# STM32.net
KiCad netlist of a schematic drawn in Altium Designer
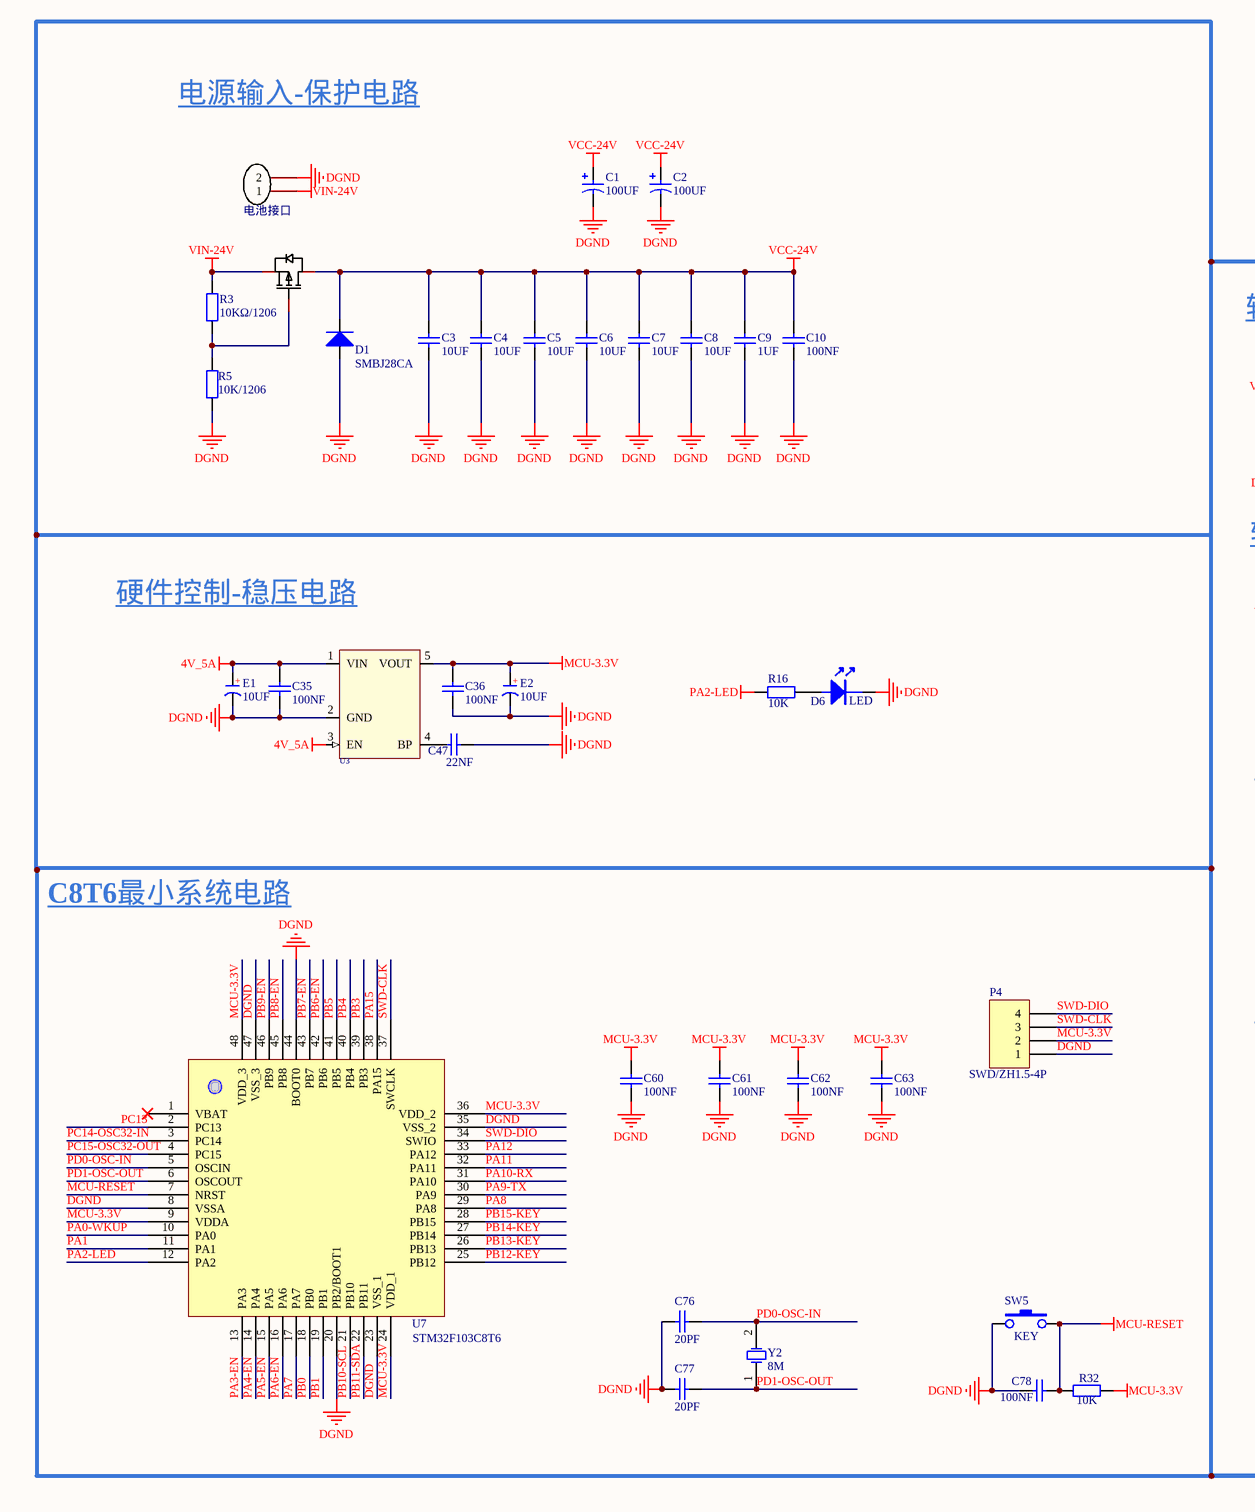
[diagram p0: 稳压板STM32.SchDoc, left]
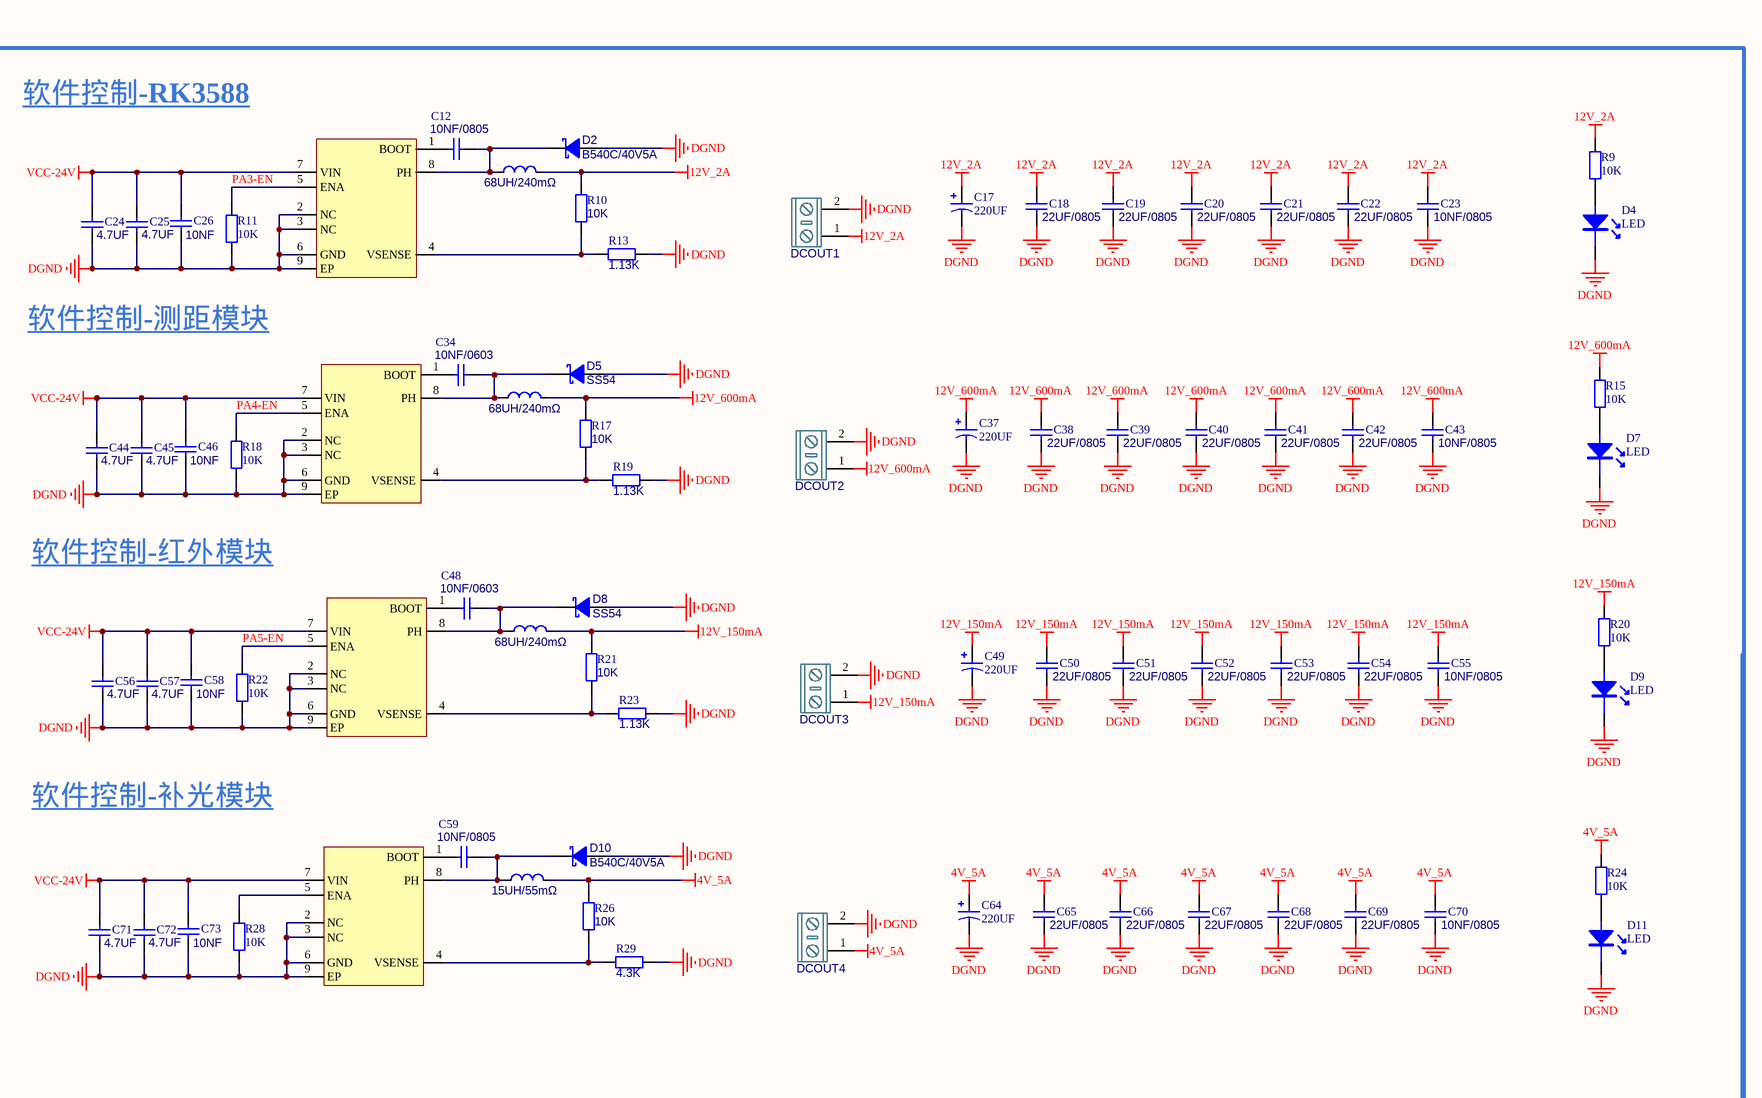
[diagram p1: 稳压板STM32.SchDoc, right]

(export (version "E")
  (design (tool "Eeschema 10.0.6"))
  (components
    (comp (ref "1")
      (value "68UH/240mΩ")
      (footprint "IND-SMD_L11.5-W10.0_SMMS1040")
      (fields
        (field (name "MANUFACTURER") "PANASONIC(松下)")
        (field (name "MANUFACTURER PART") "ETQP5M220YFM")
        (field (name "TOLERANCE") "±20%")
      )
      (libsource (lib "C8T6主控") (part "L?"))
    )
    (comp (ref "3")
      (value "68UH/240mΩ")
      (footprint "IND-SMD_L11.5-W10.0_SMMS1040")
      (fields
        (field (name "MANUFACTURER") "PANASONIC(松下)")
        (field (name "MANUFACTURER PART") "ETQP5M220YFM")
        (field (name "TOLERANCE") "±20%")
      )
      (libsource (lib "") (part "L?_1"))
    )
    (comp (ref "4")
      (value "68UH/240mΩ")
      (footprint "IND-SMD_L11.5-W10.0_SMMS1040")
      (fields
        (field (name "MANUFACTURER") "PANASONIC(松下)")
        (field (name "MANUFACTURER PART") "ETQP5M220YFM")
        (field (name "TOLERANCE") "±20%")
      )
      (libsource (lib "") (part "L?_3"))
    )
    (comp (ref "5")
      (value "15UH/55mΩ")
      (footprint "IND-SMD_L11.5-W10.0_SMMS1040")
      (fields
        (field (name "MANUFACTURER") "PANASONIC(松下)")
        (field (name "MANUFACTURER PART") "ETQP5M220YFM")
        (field (name "TOLERANCE") "±20%")
      )
      (libsource (lib "") (part "L?_2"))
    )
    (comp (ref "C1")
      (value "100UF")
      (footprint "CM D(6.3*7.7)")
      (description "有极性电容")
      (fields (field (name "PUBLISHER") "Altium Limited"))
      (libsource (lib "C8T6主控") (part "Cap Pol"))
    )
    (comp (ref "C2")
      (value "100UF")
      (footprint "CM D(6.3*7.7)")
      (description "有极性电容")
      (fields (field (name "PUBLISHER") "Altium Limited"))
      (libsource (lib "C8T6主控") (part "Cap Pol"))
    )
    (comp (ref "C3")
      (value "10UF")
      (footprint "C0603")
      (description "Capacitor")
      (fields (field (name "PUBLISHER") "Altium Limited"))
      (libsource (lib "STM32F103C8T6") (part "Cap"))
    )
    (comp (ref "C4")
      (value "10UF")
      (footprint "C0603")
      (description "Capacitor")
      (fields (field (name "PUBLISHER") "Altium Limited"))
      (libsource (lib "STM32F103C8T6") (part "Cap"))
    )
    (comp (ref "C5")
      (value "10UF")
      (footprint "C0603")
      (description "Capacitor")
      (fields (field (name "PUBLISHER") "Altium Limited"))
      (libsource (lib "STM32F103C8T6") (part "Cap"))
    )
    (comp (ref "C6")
      (value "10UF")
      (footprint "C0603")
      (description "Capacitor")
      (fields (field (name "PUBLISHER") "Altium Limited"))
      (libsource (lib "STM32F103C8T6") (part "Cap"))
    )
    (comp (ref "C7")
      (value "10UF")
      (footprint "C0603")
      (description "Capacitor")
      (fields (field (name "PUBLISHER") "Altium Limited"))
      (libsource (lib "STM32F103C8T6") (part "Cap"))
    )
    (comp (ref "C8")
      (value "10UF")
      (footprint "C0603")
      (description "Capacitor")
      (fields (field (name "PUBLISHER") "Altium Limited"))
      (libsource (lib "STM32F103C8T6") (part "Cap"))
    )
    (comp (ref "C9")
      (value "1UF")
      (footprint "C0603")
      (description "Capacitor")
      (fields (field (name "PUBLISHER") "Altium Limited"))
      (libsource (lib "STM32F103C8T6") (part "Cap"))
    )
    (comp (ref "C10")
      (value "100NF")
      (footprint "C0603")
      (description "Capacitor")
      (fields (field (name "PUBLISHER") "Altium Limited"))
      (libsource (lib "STM32F103C8T6") (part "Cap"))
    )
    (comp (ref "C12")
      (value "10NF/0805")
      (footprint "C0805")
      (description "Capacitor")
      (fields (field (name "PUBLISHER") "Altium Limited"))
      (libsource (lib "STM32F103C8T6") (part "Cap"))
    )
    (comp (ref "C17")
      (value "220UF")
      (footprint "CM F(10*10.2)")
      (description "有极性电容")
      (fields (field (name "PUBLISHER") "Altium Limited"))
      (libsource (lib "C8T6主控") (part "Cap Pol"))
    )
    (comp (ref "C18")
      (value "22UF/0805")
      (footprint "C0805")
      (description "Capacitor")
      (fields (field (name "PUBLISHER") "Altium Limited"))
      (libsource (lib "STM32F103C8T6") (part "Cap"))
    )
    (comp (ref "C19")
      (value "22UF/0805")
      (footprint "C0805")
      (description "Capacitor")
      (fields (field (name "PUBLISHER") "Altium Limited"))
      (libsource (lib "STM32F103C8T6") (part "Cap"))
    )
    (comp (ref "C20")
      (value "22UF/0805")
      (footprint "C0805")
      (description "Capacitor")
      (fields (field (name "PUBLISHER") "Altium Limited"))
      (libsource (lib "STM32F103C8T6") (part "Cap"))
    )
    (comp (ref "C21")
      (value "22UF/0805")
      (footprint "C0805")
      (description "Capacitor")
      (fields (field (name "PUBLISHER") "Altium Limited"))
      (libsource (lib "STM32F103C8T6") (part "Cap"))
    )
    (comp (ref "C22")
      (value "22UF/0805")
      (footprint "C0805")
      (description "Capacitor")
      (fields (field (name "PUBLISHER") "Altium Limited"))
      (libsource (lib "STM32F103C8T6") (part "Cap"))
    )
    (comp (ref "C23")
      (value "10NF/0805")
      (footprint "C0805")
      (description "Capacitor")
      (fields (field (name "PUBLISHER") "Altium Limited"))
      (libsource (lib "STM32F103C8T6") (part "Cap"))
    )
    (comp (ref "C24")
      (value "4.7UF")
      (footprint "C1812")
      (description "Capacitor")
      (fields (field (name "PUBLISHER") "Altium Limited"))
      (libsource (lib "STM32F103C8T6") (part "Cap"))
    )
    (comp (ref "C25")
      (value "4.7UF")
      (footprint "C1812")
      (description "Capacitor")
      (fields (field (name "PUBLISHER") "Altium Limited"))
      (libsource (lib "STM32F103C8T6") (part "Cap"))
    )
    (comp (ref "C26")
      (value "10NF")
      (footprint "C0805")
      (description "Capacitor")
      (fields (field (name "PUBLISHER") "Altium Limited"))
      (libsource (lib "STM32F103C8T6") (part "Cap"))
    )
    (comp (ref "C34")
      (value "10NF/0603")
      (footprint "C0603")
      (description "Capacitor")
      (fields (field (name "PUBLISHER") "Altium Limited"))
      (libsource (lib "STM32F103C8T6") (part "Cap"))
    )
    (comp (ref "C35")
      (value "100NF")
      (footprint "C0603")
      (description "Capacitor")
      (fields (field (name "PUBLISHER") "Altium Limited"))
      (libsource (lib "STM32F103C8T6") (part "Cap"))
    )
    (comp (ref "C36")
      (value "100NF")
      (footprint "C0603")
      (description "Capacitor")
      (fields (field (name "PUBLISHER") "Altium Limited"))
      (libsource (lib "STM32F103C8T6") (part "Cap"))
    )
    (comp (ref "C37")
      (value "220UF")
      (footprint "CM F(10*10.2)")
      (description "有极性电容")
      (fields (field (name "PUBLISHER") "Altium Limited"))
      (libsource (lib "C8T6主控") (part "Cap Pol"))
    )
    (comp (ref "C38")
      (value "22UF/0805")
      (footprint "C0805")
      (description "Capacitor")
      (fields (field (name "PUBLISHER") "Altium Limited"))
      (libsource (lib "STM32F103C8T6") (part "Cap"))
    )
    (comp (ref "C39")
      (value "22UF/0805")
      (footprint "C0805")
      (description "Capacitor")
      (fields (field (name "PUBLISHER") "Altium Limited"))
      (libsource (lib "STM32F103C8T6") (part "Cap"))
    )
    (comp (ref "C40")
      (value "22UF/0805")
      (footprint "C0805")
      (description "Capacitor")
      (fields (field (name "PUBLISHER") "Altium Limited"))
      (libsource (lib "STM32F103C8T6") (part "Cap"))
    )
    (comp (ref "C41")
      (value "22UF/0805")
      (footprint "C0805")
      (description "Capacitor")
      (fields (field (name "PUBLISHER") "Altium Limited"))
      (libsource (lib "STM32F103C8T6") (part "Cap"))
    )
    (comp (ref "C42")
      (value "22UF/0805")
      (footprint "C0805")
      (description "Capacitor")
      (fields (field (name "PUBLISHER") "Altium Limited"))
      (libsource (lib "STM32F103C8T6") (part "Cap"))
    )
    (comp (ref "C43")
      (value "10NF/0805")
      (footprint "C0805")
      (description "Capacitor")
      (fields (field (name "PUBLISHER") "Altium Limited"))
      (libsource (lib "STM32F103C8T6") (part "Cap"))
    )
    (comp (ref "C44")
      (value "4.7UF")
      (footprint "C0603")
      (description "Capacitor")
      (fields (field (name "PUBLISHER") "Altium Limited"))
      (libsource (lib "STM32F103C8T6") (part "Cap"))
    )
    (comp (ref "C45")
      (value "4.7UF")
      (footprint "C0603")
      (description "Capacitor")
      (fields (field (name "PUBLISHER") "Altium Limited"))
      (libsource (lib "STM32F103C8T6") (part "Cap"))
    )
    (comp (ref "C46")
      (value "10NF")
      (footprint "C0603")
      (description "Capacitor")
      (fields (field (name "PUBLISHER") "Altium Limited"))
      (libsource (lib "STM32F103C8T6") (part "Cap"))
    )
    (comp (ref "C47")
      (value "22NF")
      (footprint "C0603")
      (description "Capacitor")
      (fields (field (name "PUBLISHER") "Altium Limited"))
      (libsource (lib "STM32F103C8T6") (part "Cap"))
    )
    (comp (ref "C48")
      (value "10NF/0603")
      (footprint "C0603")
      (description "Capacitor")
      (fields (field (name "PUBLISHER") "Altium Limited"))
      (libsource (lib "STM32F103C8T6") (part "Cap"))
    )
    (comp (ref "C49")
      (value "220UF")
      (footprint "CM F(10*10.2)")
      (description "有极性电容")
      (fields (field (name "PUBLISHER") "Altium Limited"))
      (libsource (lib "C8T6主控") (part "Cap Pol"))
    )
    (comp (ref "C50")
      (value "22UF/0805")
      (footprint "C0805")
      (description "Capacitor")
      (fields (field (name "PUBLISHER") "Altium Limited"))
      (libsource (lib "STM32F103C8T6") (part "Cap"))
    )
    (comp (ref "C51")
      (value "22UF/0805")
      (footprint "C0805")
      (description "Capacitor")
      (fields (field (name "PUBLISHER") "Altium Limited"))
      (libsource (lib "STM32F103C8T6") (part "Cap"))
    )
    (comp (ref "C52")
      (value "22UF/0805")
      (footprint "C0805")
      (description "Capacitor")
      (fields (field (name "PUBLISHER") "Altium Limited"))
      (libsource (lib "STM32F103C8T6") (part "Cap"))
    )
    (comp (ref "C53")
      (value "22UF/0805")
      (footprint "C0805")
      (description "Capacitor")
      (fields (field (name "PUBLISHER") "Altium Limited"))
      (libsource (lib "STM32F103C8T6") (part "Cap"))
    )
    (comp (ref "C54")
      (value "22UF/0805")
      (footprint "C0805")
      (description "Capacitor")
      (fields (field (name "PUBLISHER") "Altium Limited"))
      (libsource (lib "STM32F103C8T6") (part "Cap"))
    )
    (comp (ref "C55")
      (value "10NF/0805")
      (footprint "C0805")
      (description "Capacitor")
      (fields (field (name "PUBLISHER") "Altium Limited"))
      (libsource (lib "STM32F103C8T6") (part "Cap"))
    )
    (comp (ref "C56")
      (value "4.7UF")
      (footprint "C0603")
      (description "Capacitor")
      (fields (field (name "PUBLISHER") "Altium Limited"))
      (libsource (lib "STM32F103C8T6") (part "Cap"))
    )
    (comp (ref "C57")
      (value "4.7UF")
      (footprint "C0603")
      (description "Capacitor")
      (fields (field (name "PUBLISHER") "Altium Limited"))
      (libsource (lib "STM32F103C8T6") (part "Cap"))
    )
    (comp (ref "C58")
      (value "10NF")
      (footprint "C0603")
      (description "Capacitor")
      (fields (field (name "PUBLISHER") "Altium Limited"))
      (libsource (lib "STM32F103C8T6") (part "Cap"))
    )
    (comp (ref "C59")
      (value "10NF/0805")
      (footprint "C0805")
      (description "Capacitor")
      (fields (field (name "PUBLISHER") "Altium Limited"))
      (libsource (lib "STM32F103C8T6") (part "Cap"))
    )
    (comp (ref "C60")
      (value "100NF")
      (footprint "C0603")
      (description "Capacitor")
      (fields (field (name "PUBLISHER") "Altium Limited"))
      (libsource (lib "STM32F103C8T6") (part "Cap"))
    )
    (comp (ref "C61")
      (value "100NF")
      (footprint "C0603")
      (description "Capacitor")
      (fields (field (name "PUBLISHER") "Altium Limited"))
      (libsource (lib "STM32F103C8T6") (part "Cap"))
    )
    (comp (ref "C62")
      (value "100NF")
      (footprint "C0603")
      (description "Capacitor")
      (fields (field (name "PUBLISHER") "Altium Limited"))
      (libsource (lib "STM32F103C8T6") (part "Cap"))
    )
    (comp (ref "C63")
      (value "100NF")
      (footprint "C0603")
      (description "Capacitor")
      (fields (field (name "PUBLISHER") "Altium Limited"))
      (libsource (lib "STM32F103C8T6") (part "Cap"))
    )
    (comp (ref "C64")
      (value "220UF")
      (footprint "CM F(10*10.2)")
      (description "有极性电容")
      (fields (field (name "PUBLISHER") "Altium Limited"))
      (libsource (lib "C8T6主控") (part "Cap Pol"))
    )
    (comp (ref "C65")
      (value "22UF/0805")
      (footprint "C0805")
      (description "Capacitor")
      (fields (field (name "PUBLISHER") "Altium Limited"))
      (libsource (lib "STM32F103C8T6") (part "Cap"))
    )
    (comp (ref "C66")
      (value "22UF/0805")
      (footprint "C0805")
      (description "Capacitor")
      (fields (field (name "PUBLISHER") "Altium Limited"))
      (libsource (lib "STM32F103C8T6") (part "Cap"))
    )
    (comp (ref "C67")
      (value "22UF/0805")
      (footprint "C0805")
      (description "Capacitor")
      (fields (field (name "PUBLISHER") "Altium Limited"))
      (libsource (lib "STM32F103C8T6") (part "Cap"))
    )
    (comp (ref "C68")
      (value "22UF/0805")
      (footprint "C0805")
      (description "Capacitor")
      (fields (field (name "PUBLISHER") "Altium Limited"))
      (libsource (lib "STM32F103C8T6") (part "Cap"))
    )
    (comp (ref "C69")
      (value "22UF/0805")
      (footprint "C0805")
      (description "Capacitor")
      (fields (field (name "PUBLISHER") "Altium Limited"))
      (libsource (lib "STM32F103C8T6") (part "Cap"))
    )
    (comp (ref "C70")
      (value "10NF/0805")
      (footprint "C0805")
      (description "Capacitor")
      (fields (field (name "PUBLISHER") "Altium Limited"))
      (libsource (lib "STM32F103C8T6") (part "Cap"))
    )
    (comp (ref "C71")
      (value "4.7UF")
      (footprint "C1812")
      (description "Capacitor")
      (fields (field (name "PUBLISHER") "Altium Limited"))
      (libsource (lib "STM32F103C8T6") (part "Cap"))
    )
    (comp (ref "C72")
      (value "4.7UF")
      (footprint "C1812")
      (description "Capacitor")
      (fields (field (name "PUBLISHER") "Altium Limited"))
      (libsource (lib "STM32F103C8T6") (part "Cap"))
    )
    (comp (ref "C73")
      (value "10NF")
      (footprint "C0805")
      (description "Capacitor")
      (fields (field (name "PUBLISHER") "Altium Limited"))
      (libsource (lib "STM32F103C8T6") (part "Cap"))
    )
    (comp (ref "C76")
      (value "20PF")
      (footprint "C0603")
      (description "Capacitor")
      (fields (field (name "PUBLISHER") "Altium Limited"))
      (libsource (lib "STM32F103C8T6") (part "Cap"))
    )
    (comp (ref "C77")
      (value "20PF")
      (footprint "C0603")
      (description "Capacitor")
      (fields (field (name "PUBLISHER") "Altium Limited"))
      (libsource (lib "STM32F103C8T6") (part "Cap"))
    )
    (comp (ref "C78")
      (value "100NF")
      (footprint "C0603")
      (description "Capacitor")
      (fields (field (name "PUBLISHER") "Altium Limited"))
      (libsource (lib "STM32F103C8T6") (part "Cap"))
    )
    (comp (ref "D1")
      (value "SMBJ28CA")
      (footprint "SMB")
      (description "TVS保护")
      (fields (field (name "PUBLISHER") "Altium Limited"))
      (libsource (lib "电源管理C8T6") (part "TVS"))
    )
    (comp (ref "D2")
      (value "B540C/40V5A")
      (footprint "SMC")
      (description "SS54 肖特基二极管")
      (libsource (lib "C8T6主控") (part "SS54"))
    )
    (comp (ref "D4") (value "LED") (footprint "LEDC1608(0603)-L") (libsource (lib "C8T6主控") (part "LED")))
    (comp (ref "D5")
      (value "SS54")
      (footprint "SMA")
      (description "SS54 肖特基二极管")
      (libsource (lib "C8T6主控") (part "SS54"))
    )
    (comp (ref "D6") (value "LED") (footprint "LEDC1608(0603)-L") (libsource (lib "C8T6主控") (part "LED")))
    (comp (ref "D7") (value "LED") (footprint "LEDC1608(0603)-L") (libsource (lib "C8T6主控") (part "LED")))
    (comp (ref "D8")
      (value "SS54")
      (footprint "SMA")
      (description "SS54 肖特基二极管")
      (libsource (lib "C8T6主控") (part "SS54"))
    )
    (comp (ref "D9") (value "LED") (footprint "LEDC1608(0603)-L") (libsource (lib "C8T6主控") (part "LED")))
    (comp (ref "D10")
      (value "B540C/40V5A")
      (footprint "SMC")
      (description "SS54 肖特基二极管")
      (libsource (lib "C8T6主控") (part "SS54"))
    )
    (comp (ref "D11") (value "LED") (footprint "LEDC1608(0603)-L") (libsource (lib "C8T6主控") (part "LED")))
    (comp (ref "DCOUT1")
      (value "KF/WJ/DG 30x connecter")
      (footprint "KF128-5.08-2P")
      (description "接线端子 2Pin")
      (libsource (lib "电源管理C8T6") (part "KF/WJ/DG 30x"))
    )
    (comp (ref "DCOUT2")
      (value "KF/WJ/DG 30x connecter")
      (footprint "KF128-5.08-2P")
      (description "接线端子 2Pin")
      (libsource (lib "电源管理C8T6") (part "KF/WJ/DG 30x"))
    )
    (comp (ref "DCOUT3")
      (value "KF/WJ/DG 30x connecter")
      (footprint "KF128-5.08-2P")
      (description "接线端子 2Pin")
      (libsource (lib "电源管理C8T6") (part "KF/WJ/DG 30x"))
    )
    (comp (ref "DCOUT4")
      (value "KF/WJ/DG 30x connecter")
      (footprint "KF128-5.08-2P")
      (description "接线端子 2Pin")
      (libsource (lib "电源管理C8T6") (part "KF/WJ/DG 30x"))
    )
    (comp (ref "E1")
      (value "10UF")
      (footprint "CD A(3216)")
      (description "贴片钽电容")
      (libsource (lib "电源管理C8T6") (part "CT"))
    )
    (comp (ref "E2")
      (value "10UF")
      (footprint "CD A(3216)")
      (description "贴片钽电容")
      (libsource (lib "电源管理C8T6") (part "CT"))
    )
    (comp (ref "P1")
      (value "电池接口")
      (footprint "CONN-TH_2P-P7.62_L15.2-W16.7-EX4.2")
      (fields
        (field (name "MANUFACTURER") "KANGNEX(康奈克斯电气)")
        (field (name "MANUFACTURER PART") "WJ500V-5.08-2P")
      )
      (libsource (lib "电源管理C8T6") (part "WJ500V-5.08-2P-接线端子"))
    )
    (comp (ref "P4")
      (value "SWD/ZH1.5-4P")
      (footprint "ZH1.5-LI-4P")
      (description "Header, 4-Pin")
      (fields (field (name "PUBLISHER") "Altium Limited"))
      (libsource (lib "STM32F103C8T6") (part "Header 4"))
    )
    (comp (ref "Q2")
      (value "IRF9540NSTRLPBF")
      (footprint "TO263-2")
      (fields (field (name "MANUFACTURER") "Infineon(英飞凌)"))
      (libsource (lib "电源管理C8T6") (part "IRF9540NSTRLPBF"))
    )
    (comp (ref "R3")
      (value "10KΩ/1206")
      (footprint "R1206")
      (description "Resistor")
      (fields (field (name "PUBLISHER") "Altium Limited"))
      (libsource (lib "") (part "Res2_1"))
    )
    (comp (ref "R5")
      (value "10K/1206")
      (footprint "R1206")
      (description "Resistor")
      (fields (field (name "PUBLISHER") "Altium Limited"))
      (libsource (lib "") (part "Res2_1"))
    )
    (comp (ref "R9")
      (value "10K")
      (footprint "R0805")
      (description "Resistor")
      (fields (field (name "PUBLISHER") "Altium Limited"))
      (libsource (lib "STM32F103C8T6") (part "Res2"))
    )
    (comp (ref "R10")
      (value "10K")
      (footprint "R0805")
      (description "Resistor")
      (fields (field (name "PUBLISHER") "Altium Limited"))
      (libsource (lib "") (part "Res2_1"))
    )
    (comp (ref "R11")
      (value "10K")
      (footprint "R0805")
      (description "Resistor")
      (fields (field (name "PUBLISHER") "Altium Limited"))
      (libsource (lib "STM32F103C8T6") (part "Res2"))
    )
    (comp (ref "R13")
      (value "1.13K")
      (footprint "R0805")
      (description "Resistor")
      (fields (field (name "PUBLISHER") "Altium Limited"))
      (libsource (lib "") (part "Res2_2"))
    )
    (comp (ref "R15")
      (value "10K")
      (footprint "R0805")
      (description "Resistor")
      (fields (field (name "PUBLISHER") "Altium Limited"))
      (libsource (lib "STM32F103C8T6") (part "Res2"))
    )
    (comp (ref "R16")
      (value "10K")
      (footprint "R0805")
      (description "Resistor")
      (fields (field (name "PUBLISHER") "Altium Limited"))
      (libsource (lib "") (part "Res2_2"))
    )
    (comp (ref "R17")
      (value "10K")
      (footprint "R0805")
      (description "Resistor")
      (fields (field (name "PUBLISHER") "Altium Limited"))
      (libsource (lib "") (part "Res2_1"))
    )
    (comp (ref "R18")
      (value "10K")
      (footprint "R0805")
      (description "Resistor")
      (fields (field (name "PUBLISHER") "Altium Limited"))
      (libsource (lib "STM32F103C8T6") (part "Res2"))
    )
    (comp (ref "R19")
      (value "1.13K")
      (footprint "R0805")
      (description "Resistor")
      (fields (field (name "PUBLISHER") "Altium Limited"))
      (libsource (lib "") (part "Res2_2"))
    )
    (comp (ref "R20")
      (value "10K")
      (footprint "R0805")
      (description "Resistor")
      (fields (field (name "PUBLISHER") "Altium Limited"))
      (libsource (lib "STM32F103C8T6") (part "Res2"))
    )
    (comp (ref "R21")
      (value "10K")
      (footprint "R0805")
      (description "Resistor")
      (fields (field (name "PUBLISHER") "Altium Limited"))
      (libsource (lib "") (part "Res2_1"))
    )
    (comp (ref "R22")
      (value "10K")
      (footprint "R0805")
      (description "Resistor")
      (fields (field (name "PUBLISHER") "Altium Limited"))
      (libsource (lib "STM32F103C8T6") (part "Res2"))
    )
    (comp (ref "R23")
      (value "1.13K")
      (footprint "R0805")
      (description "Resistor")
      (fields (field (name "PUBLISHER") "Altium Limited"))
      (libsource (lib "") (part "Res2_2"))
    )
    (comp (ref "R24")
      (value "10K")
      (footprint "R0805")
      (description "Resistor")
      (fields (field (name "PUBLISHER") "Altium Limited"))
      (libsource (lib "STM32F103C8T6") (part "Res2"))
    )
    (comp (ref "R26")
      (value "10K")
      (footprint "R0805")
      (description "Resistor")
      (fields (field (name "PUBLISHER") "Altium Limited"))
      (libsource (lib "") (part "Res2_1"))
    )
    (comp (ref "R28")
      (value "10K")
      (footprint "R0805")
      (description "Resistor")
      (fields (field (name "PUBLISHER") "Altium Limited"))
      (libsource (lib "STM32F103C8T6") (part "Res2"))
    )
    (comp (ref "R29")
      (value "4.3K")
      (footprint "R0805")
      (description "Resistor")
      (fields (field (name "PUBLISHER") "Altium Limited"))
      (libsource (lib "") (part "Res2_2"))
    )
    (comp (ref "R32")
      (value "10K")
      (footprint "R0603")
      (description "Resistor")
      (fields (field (name "PUBLISHER") "Altium Limited"))
      (libsource (lib "") (part "Res2_2"))
    )
    (comp (ref "SW5")
      (value "KEY")
      (footprint "TSW SMD-3*6*2.5")
      (description "SWITCH")
      (libsource (lib "STM32F103C8T6") (part "SW-PB_V"))
    )
    (comp (ref "U1")
      (value "TPS5450DDAR")
      (footprint "SOP8")
      (fields (field (name "MANUFACTURER") "TI(德州仪器)"))
      (libsource (lib "") (part "TPS5450DDAR_1"))
    )
    (comp (ref "U3")
      (value "RT9193")
      (footprint "SOT23-5L")
      (fields (field (name "ICA_PARTNUM") "$$2191094$$RT9193-15CU5") (field (name "PART NUMBER") "TMP-13"))
      (libsource (lib "C8T6主控") (part "RT9193X_5P"))
    )
    (comp (ref "U4")
      (value "TPS5450DDAR")
      (footprint "SOP8")
      (fields (field (name "MANUFACTURER") "TI(德州仪器)"))
      (libsource (lib "C8T6主控") (part "TPS5450DDAR"))
    )
    (comp (ref "U5")
      (value "TPS5450DDAR")
      (footprint "SOP8")
      (fields (field (name "MANUFACTURER") "TI(德州仪器)"))
      (libsource (lib "") (part "TPS5450DDAR_3"))
    )
    (comp (ref "U6")
      (value "TPS5450DDAR")
      (footprint "SOP8")
      (fields (field (name "MANUFACTURER") "TI(德州仪器)"))
      (libsource (lib "") (part "TPS5450DDAR_2"))
    )
    (comp (ref "U7")
      (value "STM32F103C8T6")
      (footprint "TQFP48 7x7_L")
      (libsource (lib "STM32F103C8T6") (part "STM32F103C8T6"))
    )
    (comp (ref "Y2")
      (value "8M")
      (footprint "OSC 5032-2P")
      (description "Crystal Oscillator")
      (fields (field (name "PUBLISHER") "Altium Limited"))
      (libsource (lib "STM32F103C8T6") (part "XTAL"))
    )
  )
  (nets
    (net (code "1") (name "/PA0-WKUP") (class "Default")
      (node (ref "U7") (pin "10") (pinfunction "PA0_10") (pintype "passive"))
    )
    (net (code "2") (name "/PA1") (class "Default")
      (node (ref "U7") (pin "11") (pinfunction "PA1_11") (pintype "passive"))
    )
    (net (code "3") (name "/PA3-EN") (class "Default")
      (node (ref "R11") (pin "1") (pinfunction "1_1") (pintype "passive"))
      (node (ref "U1") (pin "5") (pinfunction "ENA_5") (pintype "passive"))
      (node (ref "U7") (pin "13") (pinfunction "PA3_13") (pintype "passive"))
    )
    (net (code "4") (name "/PA4-EN") (class "Default")
      (node (ref "R18") (pin "1") (pinfunction "1_1") (pintype "passive"))
      (node (ref "U4") (pin "5") (pinfunction "ENA_5") (pintype "passive"))
      (node (ref "U7") (pin "14") (pinfunction "PA4_14") (pintype "passive"))
    )
    (net (code "5") (name "/PA5-EN") (class "Default")
      (node (ref "R22") (pin "1") (pinfunction "1_1") (pintype "passive"))
      (node (ref "U5") (pin "5") (pinfunction "ENA_5") (pintype "passive"))
      (node (ref "U7") (pin "15") (pinfunction "PA5_15") (pintype "passive"))
    )
    (net (code "6") (name "/PA6-EN") (class "Default")
      (node (ref "U7") (pin "16") (pinfunction "PA6_16") (pintype "passive"))
    )
    (net (code "7") (name "/PA7") (class "Default")
      (node (ref "U7") (pin "17") (pinfunction "PA7_17") (pintype "passive"))
    )
    (net (code "8") (name "/PA8") (class "Default")
      (node (ref "U7") (pin "29") (pinfunction "PA8_29") (pintype "passive"))
    )
    (net (code "9") (name "/PA9-TX") (class "Default")
      (node (ref "U7") (pin "30") (pinfunction "PA9_30") (pintype "passive"))
    )
    (net (code "10") (name "/PA10-RX") (class "Default")
      (node (ref "U7") (pin "31") (pinfunction "PA10_31") (pintype "passive"))
    )
    (net (code "11") (name "/PA11") (class "Default")
      (node (ref "U7") (pin "32") (pinfunction "PA11_32") (pintype "passive"))
    )
    (net (code "12") (name "/PA12") (class "Default")
      (node (ref "U7") (pin "33") (pinfunction "PA12_33") (pintype "passive"))
    )
    (net (code "13") (name "/PA15") (class "Default")
      (node (ref "U7") (pin "38") (pinfunction "PA15_38") (pintype "passive"))
    )
    (net (code "14") (name "/PB0") (class "Default")
      (node (ref "U7") (pin "18") (pinfunction "PB0_18") (pintype "passive"))
    )
    (net (code "15") (name "/PB1") (class "Default")
      (node (ref "U7") (pin "19") (pinfunction "PB1_19") (pintype "passive"))
    )
    (net (code "16") (name "/PB3") (class "Default")
      (node (ref "U7") (pin "39") (pinfunction "PB3_39") (pintype "passive"))
    )
    (net (code "17") (name "/PB4") (class "Default")
      (node (ref "U7") (pin "40") (pinfunction "PB4_40") (pintype "passive"))
    )
    (net (code "18") (name "/PB5") (class "Default")
      (node (ref "U7") (pin "41") (pinfunction "PB5_41") (pintype "passive"))
    )
    (net (code "19") (name "/PB6-EN") (class "Default")
      (node (ref "U7") (pin "42") (pinfunction "PB6_42") (pintype "passive"))
    )
    (net (code "20") (name "/PB7-EN") (class "Default")
      (node (ref "U7") (pin "43") (pinfunction "PB7_43") (pintype "passive"))
    )
    (net (code "21") (name "/PB8-EN") (class "Default")
      (node (ref "U7") (pin "45") (pinfunction "PB8_45") (pintype "passive"))
    )
    (net (code "22") (name "/PB9-EN") (class "Default")
      (node (ref "U7") (pin "46") (pinfunction "PB9_46") (pintype "passive"))
    )
    (net (code "23") (name "/PB10-SCL") (class "Default")
      (node (ref "U7") (pin "21") (pinfunction "PB10_21") (pintype "passive"))
    )
    (net (code "24") (name "/PB11-SDA") (class "Default")
      (node (ref "U7") (pin "22") (pinfunction "PB11_22") (pintype "passive"))
    )
    (net (code "25") (name "/PB12-KEY") (class "Default")
      (node (ref "U7") (pin "25") (pinfunction "PB12_25") (pintype "passive"))
    )
    (net (code "26") (name "/PB13-KEY") (class "Default")
      (node (ref "U7") (pin "26") (pinfunction "PB13_26") (pintype "passive"))
    )
    (net (code "27") (name "/PB14-KEY") (class "Default")
      (node (ref "U7") (pin "27") (pinfunction "PB14_27") (pintype "passive"))
    )
    (net (code "28") (name "/PB15-KEY") (class "Default")
      (node (ref "U7") (pin "28") (pinfunction "PB15_28") (pintype "passive"))
    )
    (net (code "29") (name "/PC13") (class "Default")
      (node (ref "U7") (pin "2") (pinfunction "PC13_2") (pintype "passive"))
    )
    (net (code "30") (name "/PC14-OSC32-IN") (class "Default")
      (node (ref "U7") (pin "3") (pinfunction "PC14_3") (pintype "passive"))
    )
    (net (code "31") (name "/PC15-OSC32-OUT") (class "Default")
      (node (ref "U7") (pin "4") (pinfunction "PC15_4") (pintype "passive"))
    )
    (net (code "32") (name "/PD0-OSC-IN") (class "Default")
      (node (ref "C76") (pin "1") (pinfunction "1_1") (pintype "passive"))
      (node (ref "U7") (pin "5") (pinfunction "OSCIN_5") (pintype "passive"))
      (node (ref "Y2") (pin "2") (pinfunction "OSC2_2") (pintype "passive"))
    )
    (net (code "33") (name "/PD1-OSC-OUT") (class "Default")
      (node (ref "C77") (pin "1") (pinfunction "1_1") (pintype "passive"))
      (node (ref "U7") (pin "6") (pinfunction "OSCOUT_6") (pintype "passive"))
      (node (ref "Y2") (pin "1") (pinfunction "OSC1_1") (pintype "passive"))
    )
    (net (code "34") (name "/SWD-CLK") (class "Default")
      (node (ref "P4") (pin "3") (pinfunction "3_3") (pintype "passive"))
      (node (ref "U7") (pin "37") (pinfunction "SWCLK_37") (pintype "passive"))
    )
    (net (code "35") (name "/SWD-DIO") (class "Default")
      (node (ref "P4") (pin "4") (pinfunction "4_4") (pintype "passive"))
      (node (ref "U7") (pin "34") (pinfunction "SWIO_34") (pintype "passive"))
    )
    (net (code "36") (name "4V_5A") (class "Default")
      (node (ref "5") (pin "2") (pinfunction "2_2") (pintype "passive"))
      (node (ref "C35") (pin "2") (pinfunction "2_2") (pintype "passive"))
      (node (ref "C64") (pin "1") (pinfunction "1_1") (pintype "passive"))
      (node (ref "C65") (pin "1") (pinfunction "1_1") (pintype "passive"))
      (node (ref "C66") (pin "1") (pinfunction "1_1") (pintype "passive"))
      (node (ref "C67") (pin "1") (pinfunction "1_1") (pintype "passive"))
      (node (ref "C68") (pin "1") (pinfunction "1_1") (pintype "passive"))
      (node (ref "C69") (pin "1") (pinfunction "1_1") (pintype "passive"))
      (node (ref "C70") (pin "1") (pinfunction "1_1") (pintype "passive"))
      (node (ref "DCOUT4") (pin "1") (pinfunction "1_1") (pintype "passive"))
      (node (ref "E1") (pin "1") (pinfunction "A_1") (pintype "passive"))
      (node (ref "R24") (pin "1") (pinfunction "1_1") (pintype "passive"))
      (node (ref "R26") (pin "2") (pinfunction "2_2") (pintype "passive"))
      (node (ref "U3") (pin "1") (pinfunction "VIN_1") (pintype "power_in"))
      (node (ref "U3") (pin "3") (pinfunction "EN_3") (pintype "input"))
    )
    (net (code "37") (name "12V_2A") (class "Default")
      (node (ref "1") (pin "2") (pinfunction "2_2") (pintype "passive"))
      (node (ref "C17") (pin "1") (pinfunction "1_1") (pintype "passive"))
      (node (ref "C18") (pin "1") (pinfunction "1_1") (pintype "passive"))
      (node (ref "C19") (pin "1") (pinfunction "1_1") (pintype "passive"))
      (node (ref "C20") (pin "1") (pinfunction "1_1") (pintype "passive"))
      (node (ref "C21") (pin "1") (pinfunction "1_1") (pintype "passive"))
      (node (ref "C22") (pin "1") (pinfunction "1_1") (pintype "passive"))
      (node (ref "C23") (pin "1") (pinfunction "1_1") (pintype "passive"))
      (node (ref "DCOUT1") (pin "1") (pinfunction "1_1") (pintype "passive"))
      (node (ref "R10") (pin "2") (pinfunction "2_2") (pintype "passive"))
      (node (ref "R9") (pin "1") (pinfunction "1_1") (pintype "passive"))
    )
    (net (code "38") (name "12V_150mA") (class "Default")
      (node (ref "4") (pin "2") (pinfunction "2_2") (pintype "passive"))
      (node (ref "C49") (pin "1") (pinfunction "1_1") (pintype "passive"))
      (node (ref "C50") (pin "1") (pinfunction "1_1") (pintype "passive"))
      (node (ref "C51") (pin "1") (pinfunction "1_1") (pintype "passive"))
      (node (ref "C52") (pin "1") (pinfunction "1_1") (pintype "passive"))
      (node (ref "C53") (pin "1") (pinfunction "1_1") (pintype "passive"))
      (node (ref "C54") (pin "1") (pinfunction "1_1") (pintype "passive"))
      (node (ref "C55") (pin "1") (pinfunction "1_1") (pintype "passive"))
      (node (ref "DCOUT3") (pin "1") (pinfunction "1_1") (pintype "passive"))
      (node (ref "R20") (pin "1") (pinfunction "1_1") (pintype "passive"))
      (node (ref "R21") (pin "2") (pinfunction "2_2") (pintype "passive"))
    )
    (net (code "39") (name "12V_600mA") (class "Default")
      (node (ref "3") (pin "2") (pinfunction "2_2") (pintype "passive"))
      (node (ref "C37") (pin "1") (pinfunction "1_1") (pintype "passive"))
      (node (ref "C38") (pin "1") (pinfunction "1_1") (pintype "passive"))
      (node (ref "C39") (pin "1") (pinfunction "1_1") (pintype "passive"))
      (node (ref "C40") (pin "1") (pinfunction "1_1") (pintype "passive"))
      (node (ref "C41") (pin "1") (pinfunction "1_1") (pintype "passive"))
      (node (ref "C42") (pin "1") (pinfunction "1_1") (pintype "passive"))
      (node (ref "C43") (pin "1") (pinfunction "1_1") (pintype "passive"))
      (node (ref "DCOUT2") (pin "1") (pinfunction "1_1") (pintype "passive"))
      (node (ref "R15") (pin "1") (pinfunction "1_1") (pintype "passive"))
      (node (ref "R17") (pin "2") (pinfunction "2_2") (pintype "passive"))
    )
    (net (code "40") (name "DGND") (class "Default")
      (node (ref "C1") (pin "2") (pinfunction "2_2") (pintype "passive"))
      (node (ref "C10") (pin "2") (pinfunction "2_2") (pintype "passive"))
      (node (ref "C17") (pin "2") (pinfunction "2_2") (pintype "passive"))
      (node (ref "C18") (pin "2") (pinfunction "2_2") (pintype "passive"))
      (node (ref "C19") (pin "2") (pinfunction "2_2") (pintype "passive"))
      (node (ref "C2") (pin "2") (pinfunction "2_2") (pintype "passive"))
      (node (ref "C20") (pin "2") (pinfunction "2_2") (pintype "passive"))
      (node (ref "C21") (pin "2") (pinfunction "2_2") (pintype "passive"))
      (node (ref "C22") (pin "2") (pinfunction "2_2") (pintype "passive"))
      (node (ref "C23") (pin "2") (pinfunction "2_2") (pintype "passive"))
      (node (ref "C24") (pin "1") (pinfunction "1_1") (pintype "passive"))
      (node (ref "C25") (pin "1") (pinfunction "1_1") (pintype "passive"))
      (node (ref "C26") (pin "1") (pinfunction "1_1") (pintype "passive"))
      (node (ref "C3") (pin "2") (pinfunction "2_2") (pintype "passive"))
      (node (ref "C35") (pin "1") (pinfunction "1_1") (pintype "passive"))
      (node (ref "C36") (pin "1") (pinfunction "1_1") (pintype "passive"))
      (node (ref "C37") (pin "2") (pinfunction "2_2") (pintype "passive"))
      (node (ref "C38") (pin "2") (pinfunction "2_2") (pintype "passive"))
      (node (ref "C39") (pin "2") (pinfunction "2_2") (pintype "passive"))
      (node (ref "C4") (pin "2") (pinfunction "2_2") (pintype "passive"))
      (node (ref "C40") (pin "2") (pinfunction "2_2") (pintype "passive"))
      (node (ref "C41") (pin "2") (pinfunction "2_2") (pintype "passive"))
      (node (ref "C42") (pin "2") (pinfunction "2_2") (pintype "passive"))
      (node (ref "C43") (pin "2") (pinfunction "2_2") (pintype "passive"))
      (node (ref "C44") (pin "1") (pinfunction "1_1") (pintype "passive"))
      (node (ref "C45") (pin "1") (pinfunction "1_1") (pintype "passive"))
      (node (ref "C46") (pin "1") (pinfunction "1_1") (pintype "passive"))
      (node (ref "C47") (pin "1") (pinfunction "1_1") (pintype "passive"))
      (node (ref "C49") (pin "2") (pinfunction "2_2") (pintype "passive"))
      (node (ref "C5") (pin "2") (pinfunction "2_2") (pintype "passive"))
      (node (ref "C50") (pin "2") (pinfunction "2_2") (pintype "passive"))
      (node (ref "C51") (pin "2") (pinfunction "2_2") (pintype "passive"))
      (node (ref "C52") (pin "2") (pinfunction "2_2") (pintype "passive"))
      (node (ref "C53") (pin "2") (pinfunction "2_2") (pintype "passive"))
      (node (ref "C54") (pin "2") (pinfunction "2_2") (pintype "passive"))
      (node (ref "C55") (pin "2") (pinfunction "2_2") (pintype "passive"))
      (node (ref "C56") (pin "1") (pinfunction "1_1") (pintype "passive"))
      (node (ref "C57") (pin "1") (pinfunction "1_1") (pintype "passive"))
      (node (ref "C58") (pin "1") (pinfunction "1_1") (pintype "passive"))
      (node (ref "C6") (pin "2") (pinfunction "2_2") (pintype "passive"))
      (node (ref "C60") (pin "2") (pinfunction "2_2") (pintype "passive"))
      (node (ref "C61") (pin "2") (pinfunction "2_2") (pintype "passive"))
      (node (ref "C62") (pin "2") (pinfunction "2_2") (pintype "passive"))
      (node (ref "C63") (pin "2") (pinfunction "2_2") (pintype "passive"))
      (node (ref "C64") (pin "2") (pinfunction "2_2") (pintype "passive"))
      (node (ref "C65") (pin "2") (pinfunction "2_2") (pintype "passive"))
      (node (ref "C66") (pin "2") (pinfunction "2_2") (pintype "passive"))
      (node (ref "C67") (pin "2") (pinfunction "2_2") (pintype "passive"))
      (node (ref "C68") (pin "2") (pinfunction "2_2") (pintype "passive"))
      (node (ref "C69") (pin "2") (pinfunction "2_2") (pintype "passive"))
      (node (ref "C7") (pin "2") (pinfunction "2_2") (pintype "passive"))
      (node (ref "C70") (pin "2") (pinfunction "2_2") (pintype "passive"))
      (node (ref "C71") (pin "1") (pinfunction "1_1") (pintype "passive"))
      (node (ref "C72") (pin "1") (pinfunction "1_1") (pintype "passive"))
      (node (ref "C73") (pin "1") (pinfunction "1_1") (pintype "passive"))
      (node (ref "C76") (pin "2") (pinfunction "2_2") (pintype "passive"))
      (node (ref "C77") (pin "2") (pinfunction "2_2") (pintype "passive"))
      (node (ref "C78") (pin "1") (pinfunction "1_1") (pintype "passive"))
      (node (ref "C8") (pin "2") (pinfunction "2_2") (pintype "passive"))
      (node (ref "C9") (pin "2") (pinfunction "2_2") (pintype "passive"))
      (node (ref "D1") (pin "1") (pinfunction "A_1") (pintype "passive"))
      (node (ref "D10") (pin "1") (pinfunction "1_1") (pintype "passive"))
      (node (ref "D11") (pin "2") (pinfunction "2_2") (pintype "passive"))
      (node (ref "D2") (pin "1") (pinfunction "1_1") (pintype "passive"))
      (node (ref "D4") (pin "2") (pinfunction "2_2") (pintype "passive"))
      (node (ref "D5") (pin "1") (pinfunction "1_1") (pintype "passive"))
      (node (ref "D6") (pin "2") (pinfunction "2_2") (pintype "passive"))
      (node (ref "D7") (pin "2") (pinfunction "2_2") (pintype "passive"))
      (node (ref "D8") (pin "1") (pinfunction "1_1") (pintype "passive"))
      (node (ref "D9") (pin "2") (pinfunction "2_2") (pintype "passive"))
      (node (ref "DCOUT1") (pin "2") (pinfunction "2_2") (pintype "passive"))
      (node (ref "DCOUT2") (pin "2") (pinfunction "2_2") (pintype "passive"))
      (node (ref "DCOUT3") (pin "2") (pinfunction "2_2") (pintype "passive"))
      (node (ref "DCOUT4") (pin "2") (pinfunction "2_2") (pintype "passive"))
      (node (ref "E1") (pin "2") (pinfunction "K_2") (pintype "passive"))
      (node (ref "E2") (pin "2") (pinfunction "K_2") (pintype "passive"))
      (node (ref "P1") (pin "2") (pinfunction "2_2") (pintype "passive"))
      (node (ref "P4") (pin "1") (pinfunction "1_1") (pintype "passive"))
      (node (ref "R11") (pin "2") (pinfunction "2_2") (pintype "passive"))
      (node (ref "R13") (pin "2") (pinfunction "2_2") (pintype "passive"))
      (node (ref "R18") (pin "2") (pinfunction "2_2") (pintype "passive"))
      (node (ref "R19") (pin "2") (pinfunction "2_2") (pintype "passive"))
      (node (ref "R22") (pin "2") (pinfunction "2_2") (pintype "passive"))
      (node (ref "R23") (pin "2") (pinfunction "2_2") (pintype "passive"))
      (node (ref "R28") (pin "2") (pinfunction "2_2") (pintype "passive"))
      (node (ref "R29") (pin "2") (pinfunction "2_2") (pintype "passive"))
      (node (ref "R5") (pin "1") (pinfunction "1_1") (pintype "passive"))
      (node (ref "SW5") (pin "1") (pinfunction "1_1") (pintype "passive"))
      (node (ref "U1") (pin "2") (pinfunction "NC_2") (pintype "passive"))
      (node (ref "U1") (pin "3") (pinfunction "NC_3") (pintype "passive"))
      (node (ref "U1") (pin "6") (pinfunction "GND_6") (pintype "passive"))
      (node (ref "U1") (pin "9") (pinfunction "EP_9") (pintype "passive"))
      (node (ref "U3") (pin "2") (pinfunction "GND_2") (pintype "power_in"))
      (node (ref "U4") (pin "2") (pinfunction "NC_2") (pintype "passive"))
      (node (ref "U4") (pin "3") (pinfunction "NC_3") (pintype "passive"))
      (node (ref "U4") (pin "6") (pinfunction "GND_6") (pintype "passive"))
      (node (ref "U4") (pin "9") (pinfunction "EP_9") (pintype "passive"))
      (node (ref "U5") (pin "2") (pinfunction "NC_2") (pintype "passive"))
      (node (ref "U5") (pin "3") (pinfunction "NC_3") (pintype "passive"))
      (node (ref "U5") (pin "6") (pinfunction "GND_6") (pintype "passive"))
      (node (ref "U5") (pin "9") (pinfunction "EP_9") (pintype "passive"))
      (node (ref "U6") (pin "2") (pinfunction "NC_2") (pintype "passive"))
      (node (ref "U6") (pin "3") (pinfunction "NC_3") (pintype "passive"))
      (node (ref "U6") (pin "6") (pinfunction "GND_6") (pintype "passive"))
      (node (ref "U6") (pin "9") (pinfunction "EP_9") (pintype "passive"))
      (node (ref "U7") (pin "20") (pinfunction "PB2/BOOT1_20") (pintype "passive"))
      (node (ref "U7") (pin "23") (pinfunction "VSS_1_23") (pintype "passive"))
      (node (ref "U7") (pin "35") (pinfunction "VSS_2_35") (pintype "passive"))
      (node (ref "U7") (pin "44") (pinfunction "BOOT0_44") (pintype "passive"))
      (node (ref "U7") (pin "47") (pinfunction "VSS_3_47") (pintype "passive"))
      (node (ref "U7") (pin "8") (pinfunction "VSSA_8") (pintype "passive"))
    )
    (net (code "41") (name "MCU-3.3V") (class "Default")
      (node (ref "C36") (pin "2") (pinfunction "2_2") (pintype "passive"))
      (node (ref "C60") (pin "1") (pinfunction "1_1") (pintype "passive"))
      (node (ref "C61") (pin "1") (pinfunction "1_1") (pintype "passive"))
      (node (ref "C62") (pin "1") (pinfunction "1_1") (pintype "passive"))
      (node (ref "C63") (pin "1") (pinfunction "1_1") (pintype "passive"))
      (node (ref "E2") (pin "1") (pinfunction "A_1") (pintype "passive"))
      (node (ref "P4") (pin "2") (pinfunction "2_2") (pintype "passive"))
      (node (ref "R32") (pin "2") (pinfunction "2_2") (pintype "passive"))
      (node (ref "U3") (pin "5") (pinfunction "VOUT_5") (pintype "power_in"))
      (node (ref "U7") (pin "24") (pinfunction "VDD_1_24") (pintype "passive"))
      (node (ref "U7") (pin "36") (pinfunction "VDD_2_36") (pintype "passive"))
      (node (ref "U7") (pin "48") (pinfunction "VDD_3_48") (pintype "passive"))
      (node (ref "U7") (pin "9") (pinfunction "VDDA_9") (pintype "passive"))
    )
    (net (code "42") (name "MCU-RESET") (class "Default")
      (node (ref "C78") (pin "2") (pinfunction "2_2") (pintype "passive"))
      (node (ref "R32") (pin "1") (pinfunction "1_1") (pintype "passive"))
      (node (ref "SW5") (pin "2") (pinfunction "2_2") (pintype "passive"))
      (node (ref "U7") (pin "7") (pinfunction "NRST_7") (pintype "passive"))
    )
    (net (code "43") (name "Net-(D4-Pad1)") (class "Default")
      (node (ref "D4") (pin "1") (pinfunction "1_1") (pintype "passive"))
      (node (ref "R9") (pin "2") (pinfunction "2_2") (pintype "passive"))
    )
    (net (code "44") (name "Net-(D6-Pad1)") (class "Default")
      (node (ref "D6") (pin "1") (pinfunction "1_1") (pintype "passive"))
      (node (ref "R16") (pin "2") (pinfunction "2_2") (pintype "passive"))
    )
    (net (code "45") (name "Net-(D7-Pad1)") (class "Default")
      (node (ref "D7") (pin "1") (pinfunction "1_1") (pintype "passive"))
      (node (ref "R15") (pin "2") (pinfunction "2_2") (pintype "passive"))
    )
    (net (code "46") (name "Net-(D9-Pad1)") (class "Default")
      (node (ref "D9") (pin "1") (pinfunction "1_1") (pintype "passive"))
      (node (ref "R20") (pin "2") (pinfunction "2_2") (pintype "passive"))
    )
    (net (code "47") (name "Net-(D11-Pad1)") (class "Default")
      (node (ref "D11") (pin "1") (pinfunction "1_1") (pintype "passive"))
      (node (ref "R24") (pin "2") (pinfunction "2_2") (pintype "passive"))
    )
    (net (code "48") (name "Net-(Q2-G)") (class "Default")
      (node (ref "Q2") (pin "1") (pinfunction "G_1") (pintype "passive"))
      (node (ref "R3") (pin "1") (pinfunction "1_1") (pintype "passive"))
      (node (ref "R5") (pin "2") (pinfunction "2_2") (pintype "passive"))
    )
    (net (code "49") (name "Net-(U1-BOOT)") (class "Default")
      (node (ref "C12") (pin "2") (pinfunction "2_2") (pintype "passive"))
      (node (ref "U1") (pin "1") (pinfunction "BOOT_1") (pintype "passive"))
    )
    (net (code "50") (name "Net-(U1-PH)") (class "Default")
      (node (ref "1") (pin "1") (pinfunction "1_1") (pintype "passive"))
      (node (ref "C12") (pin "1") (pinfunction "1_1") (pintype "passive"))
      (node (ref "D2") (pin "2") (pinfunction "2_2") (pintype "passive"))
      (node (ref "U1") (pin "8") (pinfunction "PH_8") (pintype "passive"))
    )
    (net (code "51") (name "Net-(U1-VSENSE)") (class "Default")
      (node (ref "R10") (pin "1") (pinfunction "1_1") (pintype "passive"))
      (node (ref "R13") (pin "1") (pinfunction "1_1") (pintype "passive"))
      (node (ref "U1") (pin "4") (pinfunction "VSENSE_4") (pintype "passive"))
    )
    (net (code "52") (name "Net-(U3-BP)") (class "Default")
      (node (ref "C47") (pin "2") (pinfunction "2_2") (pintype "passive"))
      (node (ref "U3") (pin "4") (pinfunction "BP_4") (pintype "passive"))
    )
    (net (code "53") (name "Net-(U4-BOOT)") (class "Default")
      (node (ref "C34") (pin "2") (pinfunction "2_2") (pintype "passive"))
      (node (ref "U4") (pin "1") (pinfunction "BOOT_1") (pintype "passive"))
    )
    (net (code "54") (name "Net-(U4-PH)") (class "Default")
      (node (ref "3") (pin "1") (pinfunction "1_1") (pintype "passive"))
      (node (ref "C34") (pin "1") (pinfunction "1_1") (pintype "passive"))
      (node (ref "D5") (pin "2") (pinfunction "2_2") (pintype "passive"))
      (node (ref "U4") (pin "8") (pinfunction "PH_8") (pintype "passive"))
    )
    (net (code "55") (name "Net-(U4-VSENSE)") (class "Default")
      (node (ref "R17") (pin "1") (pinfunction "1_1") (pintype "passive"))
      (node (ref "R19") (pin "1") (pinfunction "1_1") (pintype "passive"))
      (node (ref "U4") (pin "4") (pinfunction "VSENSE_4") (pintype "passive"))
    )
    (net (code "56") (name "Net-(U5-BOOT)") (class "Default")
      (node (ref "C48") (pin "2") (pinfunction "2_2") (pintype "passive"))
      (node (ref "U5") (pin "1") (pinfunction "BOOT_1") (pintype "passive"))
    )
    (net (code "57") (name "Net-(U5-PH)") (class "Default")
      (node (ref "4") (pin "1") (pinfunction "1_1") (pintype "passive"))
      (node (ref "C48") (pin "1") (pinfunction "1_1") (pintype "passive"))
      (node (ref "D8") (pin "2") (pinfunction "2_2") (pintype "passive"))
      (node (ref "U5") (pin "8") (pinfunction "PH_8") (pintype "passive"))
    )
    (net (code "58") (name "Net-(U5-VSENSE)") (class "Default")
      (node (ref "R21") (pin "1") (pinfunction "1_1") (pintype "passive"))
      (node (ref "R23") (pin "1") (pinfunction "1_1") (pintype "passive"))
      (node (ref "U5") (pin "4") (pinfunction "VSENSE_4") (pintype "passive"))
    )
    (net (code "59") (name "Net-(U6-BOOT)") (class "Default")
      (node (ref "C59") (pin "2") (pinfunction "2_2") (pintype "passive"))
      (node (ref "U6") (pin "1") (pinfunction "BOOT_1") (pintype "passive"))
    )
    (net (code "60") (name "Net-(U6-ENA)") (class "Default")
      (node (ref "R28") (pin "1") (pinfunction "1_1") (pintype "passive"))
      (node (ref "U6") (pin "5") (pinfunction "ENA_5") (pintype "passive"))
    )
    (net (code "61") (name "Net-(U6-PH)") (class "Default")
      (node (ref "5") (pin "1") (pinfunction "1_1") (pintype "passive"))
      (node (ref "C59") (pin "1") (pinfunction "1_1") (pintype "passive"))
      (node (ref "D10") (pin "2") (pinfunction "2_2") (pintype "passive"))
      (node (ref "U6") (pin "8") (pinfunction "PH_8") (pintype "passive"))
    )
    (net (code "62") (name "Net-(U6-VSENSE)") (class "Default")
      (node (ref "R26") (pin "1") (pinfunction "1_1") (pintype "passive"))
      (node (ref "R29") (pin "1") (pinfunction "1_1") (pintype "passive"))
      (node (ref "U6") (pin "4") (pinfunction "VSENSE_4") (pintype "passive"))
    )
    (net (code "63") (name "PA2-LED") (class "Default")
      (node (ref "R16") (pin "1") (pinfunction "1_1") (pintype "passive"))
      (node (ref "U7") (pin "12") (pinfunction "PA2_12") (pintype "passive"))
    )
    (net (code "64") (name "VCC-24V") (class "Default")
      (node (ref "C1") (pin "1") (pinfunction "1_1") (pintype "passive"))
      (node (ref "C10") (pin "1") (pinfunction "1_1") (pintype "passive"))
      (node (ref "C2") (pin "1") (pinfunction "1_1") (pintype "passive"))
      (node (ref "C24") (pin "2") (pinfunction "2_2") (pintype "passive"))
      (node (ref "C25") (pin "2") (pinfunction "2_2") (pintype "passive"))
      (node (ref "C26") (pin "2") (pinfunction "2_2") (pintype "passive"))
      (node (ref "C3") (pin "1") (pinfunction "1_1") (pintype "passive"))
      (node (ref "C4") (pin "1") (pinfunction "1_1") (pintype "passive"))
      (node (ref "C44") (pin "2") (pinfunction "2_2") (pintype "passive"))
      (node (ref "C45") (pin "2") (pinfunction "2_2") (pintype "passive"))
      (node (ref "C46") (pin "2") (pinfunction "2_2") (pintype "passive"))
      (node (ref "C5") (pin "1") (pinfunction "1_1") (pintype "passive"))
      (node (ref "C56") (pin "2") (pinfunction "2_2") (pintype "passive"))
      (node (ref "C57") (pin "2") (pinfunction "2_2") (pintype "passive"))
      (node (ref "C58") (pin "2") (pinfunction "2_2") (pintype "passive"))
      (node (ref "C6") (pin "1") (pinfunction "1_1") (pintype "passive"))
      (node (ref "C7") (pin "1") (pinfunction "1_1") (pintype "passive"))
      (node (ref "C71") (pin "2") (pinfunction "2_2") (pintype "passive"))
      (node (ref "C72") (pin "2") (pinfunction "2_2") (pintype "passive"))
      (node (ref "C73") (pin "2") (pinfunction "2_2") (pintype "passive"))
      (node (ref "C8") (pin "1") (pinfunction "1_1") (pintype "passive"))
      (node (ref "C9") (pin "1") (pinfunction "1_1") (pintype "passive"))
      (node (ref "D1") (pin "2") (pinfunction "K_2") (pintype "passive"))
      (node (ref "Q2") (pin "4") (pinfunction "D_4") (pintype "passive"))
      (node (ref "U1") (pin "7") (pinfunction "VIN_7") (pintype "passive"))
      (node (ref "U4") (pin "7") (pinfunction "VIN_7") (pintype "passive"))
      (node (ref "U5") (pin "7") (pinfunction "VIN_7") (pintype "passive"))
      (node (ref "U6") (pin "7") (pinfunction "VIN_7") (pintype "passive"))
    )
    (net (code "65") (name "VIN-24V") (class "Default")
      (node (ref "P1") (pin "1") (pinfunction "1_1") (pintype "passive"))
      (node (ref "Q2") (pin "3") (pinfunction "S_3") (pintype "passive"))
      (node (ref "R3") (pin "2") (pinfunction "2_2") (pintype "passive"))
    )
    (net (code "66") (name "unconnected-(U7-VBAT-Pad1)") (class "Default")
      (node (ref "U7") (pin "1") (pinfunction "VBAT_1") (pintype "passive+no_connect"))
    )
  )
)
